# ET4207_ANDROID.net
KiCad netlist of a schematic drawn in Altium Designer
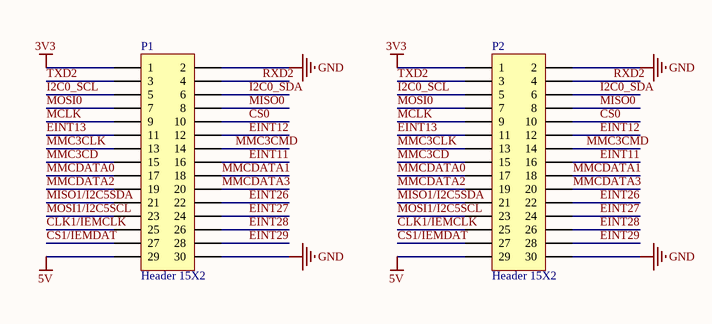
[diagram p0: ET4207_ANDROID.SchDoc]

(export (version "E")
  (design (tool "Eeschema 10.0.6"))
  (components
    (comp (ref "P1")
      (value "Header 15X2")
      (footprint "HDR2X15")
      (description "Header, 15-Pin, Dual row")
      (fields (field (name "PUBLISHER") "Altium Limited"))
      (libsource (lib "Miscellaneous Connectors") (part "Header 15X2"))
    )
    (comp (ref "P2")
      (value "Header 15X2")
      (footprint "DIP30-2.0")
      (description "Header, 15-Pin, Dual row")
      (fields (field (name "PUBLISHER") "Altium Limited"))
      (libsource (lib "Miscellaneous Connectors") (part "Header 15X2"))
    )
  )
  (nets
    (net (code "1") (name "/CLK1{slash}IEMCLK") (class "Default")
      (node (ref "P1") (pin "25") (pinfunction "25_25") (pintype "passive"))
      (node (ref "P2") (pin "25") (pinfunction "25_25") (pintype "passive"))
    )
    (net (code "2") (name "/CS0") (class "Default")
      (node (ref "P1") (pin "10") (pinfunction "10_10") (pintype "passive"))
      (node (ref "P2") (pin "10") (pinfunction "10_10") (pintype "passive"))
    )
    (net (code "3") (name "/CS1{slash}IEMDAT") (class "Default")
      (node (ref "P1") (pin "27") (pinfunction "27_27") (pintype "passive"))
      (node (ref "P2") (pin "27") (pinfunction "27_27") (pintype "passive"))
    )
    (net (code "4") (name "/EINT11") (class "Default")
      (node (ref "P1") (pin "16") (pinfunction "16_16") (pintype "passive"))
      (node (ref "P2") (pin "16") (pinfunction "16_16") (pintype "passive"))
    )
    (net (code "5") (name "/EINT12") (class "Default")
      (node (ref "P1") (pin "12") (pinfunction "12_12") (pintype "passive"))
      (node (ref "P2") (pin "12") (pinfunction "12_12") (pintype "passive"))
    )
    (net (code "6") (name "/EINT13") (class "Default")
      (node (ref "P1") (pin "11") (pinfunction "11_11") (pintype "passive"))
      (node (ref "P2") (pin "11") (pinfunction "11_11") (pintype "passive"))
    )
    (net (code "7") (name "/EINT26") (class "Default")
      (node (ref "P1") (pin "22") (pinfunction "22_22") (pintype "passive"))
      (node (ref "P2") (pin "22") (pinfunction "22_22") (pintype "passive"))
    )
    (net (code "8") (name "/EINT27") (class "Default")
      (node (ref "P1") (pin "24") (pinfunction "24_24") (pintype "passive"))
      (node (ref "P2") (pin "24") (pinfunction "24_24") (pintype "passive"))
    )
    (net (code "9") (name "/EINT28") (class "Default")
      (node (ref "P1") (pin "26") (pinfunction "26_26") (pintype "passive"))
      (node (ref "P2") (pin "26") (pinfunction "26_26") (pintype "passive"))
    )
    (net (code "10") (name "/EINT29") (class "Default")
      (node (ref "P1") (pin "28") (pinfunction "28_28") (pintype "passive"))
      (node (ref "P2") (pin "28") (pinfunction "28_28") (pintype "passive"))
    )
    (net (code "11") (name "/I2C0_SCL") (class "Default")
      (node (ref "P1") (pin "5") (pinfunction "5_5") (pintype "passive"))
      (node (ref "P2") (pin "5") (pinfunction "5_5") (pintype "passive"))
    )
    (net (code "12") (name "/I2C0_SDA") (class "Default")
      (node (ref "P1") (pin "6") (pinfunction "6_6") (pintype "passive"))
      (node (ref "P2") (pin "6") (pinfunction "6_6") (pintype "passive"))
    )
    (net (code "13") (name "/MCLK") (class "Default")
      (node (ref "P1") (pin "9") (pinfunction "9_9") (pintype "passive"))
      (node (ref "P2") (pin "9") (pinfunction "9_9") (pintype "passive"))
    )
    (net (code "14") (name "/MISO0") (class "Default")
      (node (ref "P1") (pin "8") (pinfunction "8_8") (pintype "passive"))
      (node (ref "P2") (pin "8") (pinfunction "8_8") (pintype "passive"))
    )
    (net (code "15") (name "/MISO1{slash}I2C5SDA") (class "Default")
      (node (ref "P1") (pin "21") (pinfunction "21_21") (pintype "passive"))
      (node (ref "P2") (pin "21") (pinfunction "21_21") (pintype "passive"))
    )
    (net (code "16") (name "/MMC3CD") (class "Default")
      (node (ref "P1") (pin "15") (pinfunction "15_15") (pintype "passive"))
      (node (ref "P2") (pin "15") (pinfunction "15_15") (pintype "passive"))
    )
    (net (code "17") (name "/MMC3CLK") (class "Default")
      (node (ref "P1") (pin "13") (pinfunction "13_13") (pintype "passive"))
      (node (ref "P2") (pin "13") (pinfunction "13_13") (pintype "passive"))
    )
    (net (code "18") (name "/MMC3CMD") (class "Default")
      (node (ref "P1") (pin "14") (pinfunction "14_14") (pintype "passive"))
      (node (ref "P2") (pin "14") (pinfunction "14_14") (pintype "passive"))
    )
    (net (code "19") (name "/MMCDATA0") (class "Default")
      (node (ref "P1") (pin "17") (pinfunction "17_17") (pintype "passive"))
      (node (ref "P2") (pin "17") (pinfunction "17_17") (pintype "passive"))
    )
    (net (code "20") (name "/MMCDATA1") (class "Default")
      (node (ref "P1") (pin "18") (pinfunction "18_18") (pintype "passive"))
      (node (ref "P2") (pin "18") (pinfunction "18_18") (pintype "passive"))
    )
    (net (code "21") (name "/MMCDATA2") (class "Default")
      (node (ref "P1") (pin "19") (pinfunction "19_19") (pintype "passive"))
      (node (ref "P2") (pin "19") (pinfunction "19_19") (pintype "passive"))
    )
    (net (code "22") (name "/MMCDATA3") (class "Default")
      (node (ref "P1") (pin "20") (pinfunction "20_20") (pintype "passive"))
      (node (ref "P2") (pin "20") (pinfunction "20_20") (pintype "passive"))
    )
    (net (code "23") (name "/MOSI0") (class "Default")
      (node (ref "P1") (pin "7") (pinfunction "7_7") (pintype "passive"))
      (node (ref "P2") (pin "7") (pinfunction "7_7") (pintype "passive"))
    )
    (net (code "24") (name "/MOSI1{slash}I2C5SCL") (class "Default")
      (node (ref "P1") (pin "23") (pinfunction "23_23") (pintype "passive"))
      (node (ref "P2") (pin "23") (pinfunction "23_23") (pintype "passive"))
    )
    (net (code "25") (name "/RXD2") (class "Default")
      (node (ref "P1") (pin "4") (pinfunction "4_4") (pintype "passive"))
      (node (ref "P2") (pin "4") (pinfunction "4_4") (pintype "passive"))
    )
    (net (code "26") (name "/TXD2") (class "Default")
      (node (ref "P1") (pin "3") (pinfunction "3_3") (pintype "passive"))
      (node (ref "P2") (pin "3") (pinfunction "3_3") (pintype "passive"))
    )
    (net (code "27") (name "3V3") (class "Default")
      (node (ref "P1") (pin "1") (pinfunction "1_1") (pintype "passive"))
      (node (ref "P2") (pin "1") (pinfunction "1_1") (pintype "passive"))
    )
    (net (code "28") (name "5V") (class "Default")
      (node (ref "P1") (pin "29") (pinfunction "29_29") (pintype "passive"))
      (node (ref "P2") (pin "29") (pinfunction "29_29") (pintype "passive"))
    )
    (net (code "29") (name "GND") (class "Default")
      (node (ref "P1") (pin "2") (pinfunction "2_2") (pintype "passive"))
      (node (ref "P1") (pin "30") (pinfunction "30_30") (pintype "passive"))
      (node (ref "P2") (pin "2") (pinfunction "2_2") (pintype "passive"))
      (node (ref "P2") (pin "30") (pinfunction "30_30") (pintype "passive"))
    )
  )
)
